# cpu.net
KiCad netlist of a schematic drawn in Altium Designer
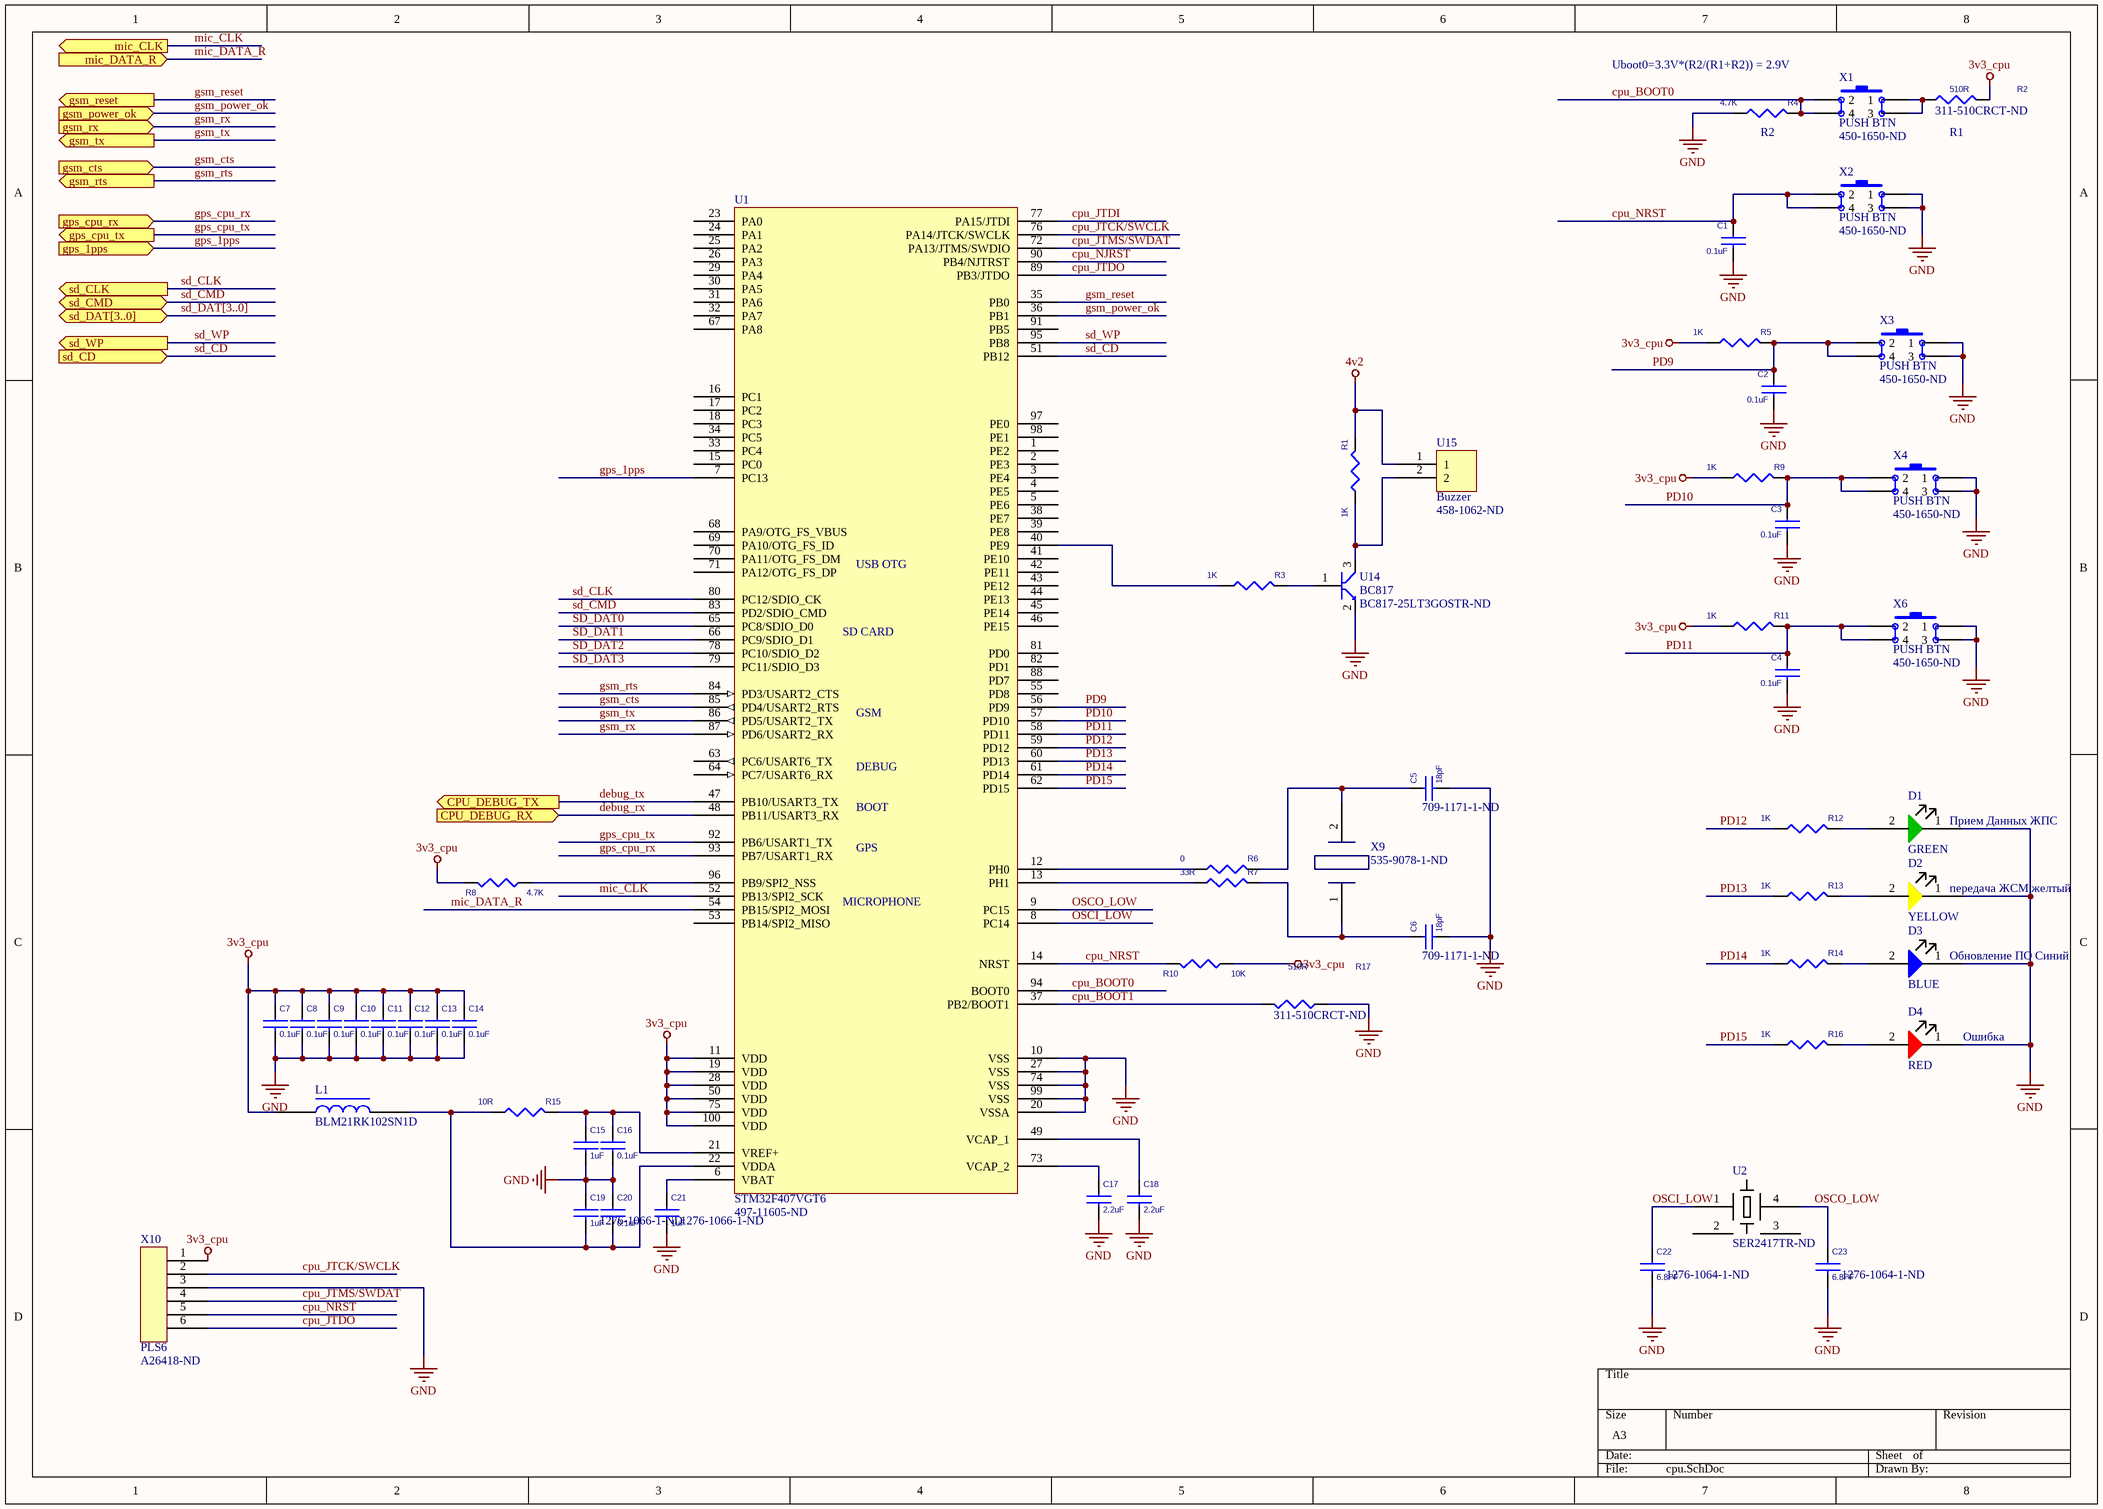
[diagram p0: cpu.SchDoc]

(export (version "E")
  (design (tool "Eeschema 10.0.6"))
  (components
    (comp (ref "C1")
      (value "0.1uF")
      (footprint "CAPC2012X09M")
      (description "CAP CER 0.1UF 25V 10% X7R 0805")
      (libsource (lib "Capacitors") (part "CAP_SMD_0.1UF_10%"))
    )
    (comp (ref "C2")
      (value "0.1uF")
      (footprint "CAPC2012X09M")
      (description "CAP CER 0.1UF 25V 10% X7R 0805")
      (libsource (lib "Capacitors") (part "CAP_SMD_0.1UF_10%"))
    )
    (comp (ref "C3")
      (value "0.1uF")
      (footprint "CAPC2012X09M")
      (description "CAP CER 0.1UF 25V 10% X7R 0805")
      (libsource (lib "Capacitors") (part "CAP_SMD_0.1UF_10%"))
    )
    (comp (ref "C4")
      (value "0.1uF")
      (footprint "CAPC2012X09M")
      (description "CAP CER 0.1UF 25V 10% X7R 0805")
      (libsource (lib "Capacitors") (part "CAP_SMD_0.1UF_10%"))
    )
    (comp (ref "C5")
      (value "18pF")
      (footprint "CAPC2012X09M")
      (description "CAP CER 27PF 200V 5% NP0 0805")
      (fields (field (name "SUPPLIER PART NUMBER 1") "709-1171-1-ND"))
      (libsource (lib "Capacitors") (part "CAP_SMD_18PF_5%"))
    )
    (comp (ref "C6")
      (value "18pF")
      (footprint "CAPC2012X09M")
      (description "CAP CER 27PF 200V 5% NP0 0805")
      (fields (field (name "SUPPLIER PART NUMBER 1") "709-1171-1-ND"))
      (libsource (lib "Capacitors") (part "CAP_SMD_18PF_5%"))
    )
    (comp (ref "C7")
      (value "0.1uF")
      (footprint "CAPC2012X09M")
      (description "CAP CER 0.1UF 25V 10% X7R 0805")
      (libsource (lib "Capacitors") (part "CAP_SMD_0.1UF_10%"))
    )
    (comp (ref "C8")
      (value "0.1uF")
      (footprint "CAPC2012X09M")
      (description "CAP CER 0.1UF 25V 10% X7R 0805")
      (libsource (lib "Capacitors") (part "CAP_SMD_0.1UF_10%"))
    )
    (comp (ref "C9")
      (value "0.1uF")
      (footprint "CAPC2012X09M")
      (description "CAP CER 0.1UF 25V 10% X7R 0805")
      (libsource (lib "Capacitors") (part "CAP_SMD_0.1UF_10%"))
    )
    (comp (ref "C10")
      (value "0.1uF")
      (footprint "CAPC2012X09M")
      (description "CAP CER 0.1UF 25V 10% X7R 0805")
      (libsource (lib "Capacitors") (part "CAP_SMD_0.1UF_10%"))
    )
    (comp (ref "C11")
      (value "0.1uF")
      (footprint "CAPC2012X09M")
      (description "CAP CER 0.1UF 25V 10% X7R 0805")
      (libsource (lib "Capacitors") (part "CAP_SMD_0.1UF_10%"))
    )
    (comp (ref "C12")
      (value "0.1uF")
      (footprint "CAPC2012X09M")
      (description "CAP CER 0.1UF 25V 10% X7R 0805")
      (libsource (lib "Capacitors") (part "CAP_SMD_0.1UF_10%"))
    )
    (comp (ref "C13")
      (value "0.1uF")
      (footprint "CAPC2012X09M")
      (description "CAP CER 0.1UF 25V 10% X7R 0805")
      (libsource (lib "Capacitors") (part "CAP_SMD_0.1UF_10%"))
    )
    (comp (ref "C14")
      (value "0.1uF")
      (footprint "CAPC2012X09M")
      (description "CAP CER 0.1UF 25V 10% X7R 0805")
      (libsource (lib "Capacitors") (part "CAP_SMD_0.1UF_10%"))
    )
    (comp (ref "C15")
      (value "1uF")
      (footprint "CAPC2012X09M")
      (description "MLCC; 1uF; 25V; X7R; ±10%; SMD; 0805;")
      (libsource (lib "Capacitors") (part "CAP_SMD_1uF_10%"))
    )
    (comp (ref "C16")
      (value "0.1uF")
      (footprint "CAPC2012X09M")
      (description "CAP CER 0.1UF 25V 10% X7R 0805")
      (libsource (lib "Capacitors") (part "CAP_SMD_0.1UF_10%"))
    )
    (comp (ref "C17")
      (value "2.2uF")
      (footprint "CAPC2012X09M")
      (description "CAP CER 2.2UF 16V 10% X5R 0805")
      (libsource (lib "Capacitors") (part "CAP_SMD_2.2uF_10%"))
    )
    (comp (ref "C18")
      (value "2.2uF")
      (footprint "CAPC2012X09M")
      (description "CAP CER 2.2UF 16V 10% X5R 0805")
      (libsource (lib "Capacitors") (part "CAP_SMD_2.2uF_10%"))
    )
    (comp (ref "C19")
      (value "1uF")
      (footprint "CAPC2012X09M")
      (description "MLCC; 1uF; 25V; X7R; ±10%; SMD; 0805;")
      (fields (field (name "SUPPLIER PART NUMBER 1") "1276-1066-1-ND"))
      (libsource (lib "Capacitors") (part "CAP_SMD_1uF_10%"))
    )
    (comp (ref "C20")
      (value "0.1uF")
      (footprint "CAPC2012X09M")
      (description "CAP CER 0.1UF 25V 10% X7R 0805")
      (libsource (lib "Capacitors") (part "CAP_SMD_0.1UF_10%"))
    )
    (comp (ref "C21")
      (value "1uF")
      (footprint "CAPC2012X09M")
      (description "MLCC; 1uF; 25V; X7R; ±10%; SMD; 0805;")
      (fields (field (name "SUPPLIER PART NUMBER 1") "1276-1066-1-ND"))
      (libsource (lib "Capacitors") (part "CAP_SMD_1uF_10%"))
    )
    (comp (ref "C22")
      (value "6.8PF")
      (footprint "CAPC2012X09M")
      (description "CAP MLCC 6.8PF 50V 5% NP0 0805")
      (fields (field (name "SUPPLIER PART NUMBER 1") "1276-1064-1-ND"))
      (libsource (lib "Capacitors") (part "CAP_SMD_6.8PF_5%"))
    )
    (comp (ref "C23")
      (value "6.8PF")
      (footprint "CAPC2012X09M")
      (description "CAP MLCC 6.8PF 50V 5% NP0 0805")
      (fields (field (name "SUPPLIER PART NUMBER 1") "1276-1064-1-ND"))
      (libsource (lib "Capacitors") (part "CAP_SMD_6.8PF_5%"))
    )
    (comp (ref "D1")
      (value "GREEN")
      (footprint "DIOC2012X11N")
      (libsource (lib "Passive") (part "LED_GREEN"))
    )
    (comp (ref "D2")
      (value "YELLOW")
      (footprint "DIOC2012X11N")
      (libsource (lib "Passive") (part "LED_YELLOW"))
    )
    (comp (ref "D3") (value "BLUE") (footprint "DIOC2012X11N") (libsource (lib "Passive") (part "LED_BLUE")))
    (comp (ref "D4") (value "RED") (footprint "DIOC2012X11N") (libsource (lib "Passive") (part "LED_RED")))
    (comp (ref "L1")
      (value "BLM21RK102SN1D")
      (footprint "DIOC2012X11N")
      (libsource (lib "Passive") (part "BLM21RK102SN1D"))
    )
    (comp (ref "R1")
      (value "1K")
      (footprint "RESC2013X06M")
      (description "RES - 1K OHM, 5%, 1/8W, 0805 SMD")
      (libsource (lib "Resistors") (part "RES_SMD_1K_5%"))
    )
    (comp (ref "R2")
      (value "510R")
      (footprint "RESC2013X06M")
      (description "RES - 510 OHM, 5%, 1/8W, 0805 SMD")
      (fields (field (name "SUPPLIER PART NUMBER 1") "311-510CRCT-ND"))
      (libsource (lib "Resistors") (part "RES_SMD_510_5%"))
    )
    (comp (ref "R3")
      (value "1K")
      (footprint "RESC2013X06M")
      (description "RES - 1K OHM, 5%, 1/8W, 0805 SMD")
      (libsource (lib "Resistors") (part "RES_SMD_1K_5%"))
    )
    (comp (ref "R4")
      (value "4.7K")
      (footprint "RESC2013X06M")
      (description "RES 4.7K OHM 1/8W 1% 0805 SMD")
      (libsource (lib "Resistors") (part "RES_SMD_4.7K_1%"))
    )
    (comp (ref "R5")
      (value "1K")
      (footprint "RESC2013X06M")
      (description "RES - 1K OHM, 5%, 1/8W, 0805 SMD")
      (libsource (lib "Resistors") (part "RES_SMD_1K_5%"))
    )
    (comp (ref "R6")
      (value "0")
      (footprint "RESC2013X06M")
      (description "RES 0.0 OHM 1/8W JUMP 0805 SMD")
      (libsource (lib "Resistors") (part "RES_SMD_0"))
    )
    (comp (ref "R7")
      (value "33R")
      (footprint "RESC2013X06M")
      (description "RES - 33 OHM, 5%, 1/8W, 0805 SMD")
      (libsource (lib "Resistors") (part "RES_SMD_33R_5%"))
    )
    (comp (ref "R8")
      (value "4.7K")
      (footprint "RESC2013X06M")
      (description "RES 4.7K OHM 1/8W 1% 0805 SMD")
      (libsource (lib "Resistors") (part "RES_SMD_4.7K_1%"))
    )
    (comp (ref "R9")
      (value "1K")
      (footprint "RESC2013X06M")
      (description "RES - 1K OHM, 5%, 1/8W, 0805 SMD")
      (libsource (lib "Resistors") (part "RES_SMD_1K_5%"))
    )
    (comp (ref "R10")
      (value "10K")
      (footprint "RESC2013X06M")
      (description "RES 10K OHM 1/8W 5% 0805 SMD")
      (libsource (lib "Resistors") (part "RES_SMD_10K_5%"))
    )
    (comp (ref "R11")
      (value "1K")
      (footprint "RESC2013X06M")
      (description "RES - 1K OHM, 5%, 1/8W, 0805 SMD")
      (libsource (lib "Resistors") (part "RES_SMD_1K_5%"))
    )
    (comp (ref "R12")
      (value "1K")
      (footprint "RESC2013X06M")
      (description "RES - 1K OHM, 5%, 1/8W, 0805 SMD")
      (libsource (lib "Resistors") (part "RES_SMD_1K_5%"))
    )
    (comp (ref "R13")
      (value "1K")
      (footprint "RESC2013X06M")
      (description "RES - 1K OHM, 5%, 1/8W, 0805 SMD")
      (libsource (lib "Resistors") (part "RES_SMD_1K_5%"))
    )
    (comp (ref "R14")
      (value "1K")
      (footprint "RESC2013X06M")
      (description "RES - 1K OHM, 5%, 1/8W, 0805 SMD")
      (libsource (lib "Resistors") (part "RES_SMD_1K_5%"))
    )
    (comp (ref "R15")
      (value "10R")
      (footprint "RESC2013X06M")
      (description "RES 10 OHM 1/8W 1% 0805 SMD")
      (libsource (lib "Resistors") (part "RES_SMD_10R_5%"))
    )
    (comp (ref "R16")
      (value "1K")
      (footprint "RESC2013X06M")
      (description "RES - 1K OHM, 5%, 1/8W, 0805 SMD")
      (libsource (lib "Resistors") (part "RES_SMD_1K_5%"))
    )
    (comp (ref "R17")
      (value "510R")
      (footprint "RESC2013X06M")
      (description "RES - 510 OHM, 5%, 1/8W, 0805 SMD")
      (fields (field (name "SUPPLIER PART NUMBER 1") "311-510CRCT-ND"))
      (libsource (lib "Resistors") (part "RES_SMD_510_5%"))
    )
    (comp (ref "U1")
      (value "STM32F407VGT6")
      (footprint "TSQFP50P1600X1600X160-100M")
      (fields (field (name "SUPPLIER PART NUMBER 1") "497-11605-ND"))
      (libsource (lib "TruthEar") (part "STM32F407VGT6"))
    )
    (comp (ref "U2")
      (value "32.768KHZ")
      (footprint "SOJ550P380X254-4M")
      (fields (field (name "SUPPLIER PART NUMBER 1") "SER2417TR-ND"))
      (libsource (lib "TruthEar") (part "MC-306"))
    )
    (comp (ref "U14")
      (value "BC817")
      (footprint "SOT95P237X111-3N_SOT-23")
      (fields (field (name "SUPPLIER PART NUMBER 1") "BC817-25LT3GOSTR-ND"))
      (libsource (lib "TruthEar") (part "BC817"))
    )
    (comp (ref "U15")
      (value "Buzzer")
      (footprint "pb1224pe")
      (fields (field (name "SUPPLIER PART NUMBER 1") "458-1062-ND"))
      (libsource (lib "TruthEar") (part "pb-1224pe-05q"))
    )
    (comp (ref "X1")
      (value "PUSH BTN")
      (footprint "PUSHBTN")
      (fields (field (name "SUPPLIER PART NUMBER 1") "450-1650-ND"))
      (libsource (lib "TruthEar") (part "SW1"))
    )
    (comp (ref "X2")
      (value "PUSH BTN")
      (footprint "PUSHBTN")
      (fields (field (name "SUPPLIER PART NUMBER 1") "450-1650-ND"))
      (libsource (lib "TruthEar") (part "SW1"))
    )
    (comp (ref "X3")
      (value "PUSH BTN")
      (footprint "PUSHBTN")
      (fields (field (name "SUPPLIER PART NUMBER 1") "450-1650-ND"))
      (libsource (lib "TruthEar") (part "SW1"))
    )
    (comp (ref "X4")
      (value "PUSH BTN")
      (footprint "PUSHBTN")
      (fields (field (name "SUPPLIER PART NUMBER 1") "450-1650-ND"))
      (libsource (lib "TruthEar") (part "SW1"))
    )
    (comp (ref "X6")
      (value "PUSH BTN")
      (footprint "PUSHBTN")
      (fields (field (name "SUPPLIER PART NUMBER 1") "450-1650-ND"))
      (libsource (lib "TruthEar") (part "SW1"))
    )
    (comp (ref "X9")
      (value "25.000Mhz")
      (footprint "SODFL1270X420-2L")
      (fields (field (name "SUPPLIER PART NUMBER 1") "535-9078-1-ND"))
      (libsource (lib "TruthEar") (part "OSC25M"))
    )
    (comp (ref "X10")
      (value "PLS6")
      (footprint "PLS6")
      (fields (field (name "SUPPLIER PART NUMBER 1") "A26418-ND"))
      (libsource (lib "Connectors") (part "PLS6"))
    )
  )
  (nets
    (net (code "5") (name "/OSCI_LOW") (class "Default")
      (node (ref "C22") (pin "1") (pinfunction "1_1") (pintype "passive"))
      (node (ref "U1") (pin "8") (pinfunction "PC14_8") (pintype "passive"))
      (node (ref "U2") (pin "1") (pinfunction "OSC1_1") (pintype "power_in"))
    )
    (net (code "6") (name "/OSCO_LOW") (class "Default")
      (node (ref "C23") (pin "1") (pinfunction "1_1") (pintype "passive"))
      (node (ref "U1") (pin "9") (pinfunction "PC15_9") (pintype "passive"))
      (node (ref "U2") (pin "4") (pinfunction "OSC2_4") (pintype "power_in"))
    )
    (net (code "7") (name "/PD9") (class "Default")
      (node (ref "C2") (pin "1") (pinfunction "1_1") (pintype "passive"))
      (node (ref "R5") (pin "2") (pinfunction "2_2") (pintype "passive"))
      (node (ref "U1") (pin "56") (pinfunction "PD9_56") (pintype "passive"))
      (node (ref "X3") (pin "2") (pinfunction "2_2") (pintype "passive"))
      (node (ref "X3") (pin "4") (pinfunction "4_4") (pintype "passive"))
    )
    (net (code "8") (name "/PD10") (class "Default")
      (node (ref "C3") (pin "1") (pinfunction "1_1") (pintype "passive"))
      (node (ref "R9") (pin "2") (pinfunction "2_2") (pintype "passive"))
      (node (ref "U1") (pin "57") (pinfunction "PD10_57") (pintype "passive"))
      (node (ref "X4") (pin "2") (pinfunction "2_2") (pintype "passive"))
      (node (ref "X4") (pin "4") (pinfunction "4_4") (pintype "passive"))
    )
    (net (code "9") (name "/PD11") (class "Default")
      (node (ref "C4") (pin "1") (pinfunction "1_1") (pintype "passive"))
      (node (ref "R11") (pin "2") (pinfunction "2_2") (pintype "passive"))
      (node (ref "U1") (pin "58") (pinfunction "PD11_58") (pintype "passive"))
      (node (ref "X6") (pin "2") (pinfunction "2_2") (pintype "passive"))
      (node (ref "X6") (pin "4") (pinfunction "4_4") (pintype "passive"))
    )
    (net (code "10") (name "/PD12") (class "Default")
      (node (ref "R12") (pin "1") (pinfunction "1_1") (pintype "passive"))
      (node (ref "U1") (pin "59") (pinfunction "PD12_59") (pintype "passive"))
    )
    (net (code "11") (name "/PD13") (class "Default")
      (node (ref "R13") (pin "1") (pinfunction "1_1") (pintype "passive"))
      (node (ref "U1") (pin "60") (pinfunction "PD13_60") (pintype "passive"))
    )
    (net (code "12") (name "/PD14") (class "Default")
      (node (ref "R14") (pin "1") (pinfunction "1_1") (pintype "passive"))
      (node (ref "U1") (pin "61") (pinfunction "PD14_61") (pintype "passive"))
    )
    (net (code "13") (name "/PD15") (class "Default")
      (node (ref "R16") (pin "1") (pinfunction "1_1") (pintype "passive"))
      (node (ref "U1") (pin "62") (pinfunction "PD15_62") (pintype "passive"))
    )
    (net (code "14") (name "/SD_DAT0") (class "Default")
      (node (ref "U1") (pin "65") (pinfunction "PC8/SDIO_D0_65") (pintype "passive"))
    )
    (net (code "15") (name "/SD_DAT1") (class "Default")
      (node (ref "U1") (pin "66") (pinfunction "PC9/SDIO_D1_66") (pintype "passive"))
    )
    (net (code "16") (name "/SD_DAT2") (class "Default")
      (node (ref "U1") (pin "78") (pinfunction "PC10/SDIO_D2_78") (pintype "passive"))
    )
    (net (code "17") (name "/SD_DAT3") (class "Default")
      (node (ref "U1") (pin "79") (pinfunction "PC11/SDIO_D3_79") (pintype "passive"))
    )
    (net (code "18") (name "/cpu_BOOT0") (class "Default")
      (node (ref "R4") (pin "2") (pinfunction "2_2") (pintype "passive"))
      (node (ref "U1") (pin "94") (pinfunction "BOOT0_94") (pintype "passive"))
      (node (ref "X1") (pin "2") (pinfunction "2_2") (pintype "passive"))
      (node (ref "X1") (pin "4") (pinfunction "4_4") (pintype "passive"))
    )
    (net (code "19") (name "/cpu_BOOT1") (class "Default")
      (node (ref "R17") (pin "2") (pinfunction "2_2") (pintype "passive"))
      (node (ref "U1") (pin "37") (pinfunction "PB2/BOOT1_37") (pintype "passive"))
    )
    (net (code "20") (name "/cpu_JTCK{slash}SWCLK") (class "Default")
      (node (ref "U1") (pin "76") (pinfunction "PA14/JTCK/SWCLK_76") (pintype "passive"))
      (node (ref "X10") (pin "2") (pinfunction "2_2") (pintype "power_in"))
    )
    (net (code "21") (name "/cpu_JTDI") (class "Default")
      (node (ref "U1") (pin "77") (pinfunction "PA15/JTDI_77") (pintype "passive"))
    )
    (net (code "22") (name "/cpu_JTDO") (class "Default")
      (node (ref "U1") (pin "89") (pinfunction "PB3/JTDO_89") (pintype "passive"))
      (node (ref "X10") (pin "6") (pinfunction "6_6") (pintype "power_in"))
    )
    (net (code "23") (name "/cpu_JTMS{slash}SWDAT") (class "Default")
      (node (ref "U1") (pin "72") (pinfunction "PA13/JTMS/SWDIO_72") (pintype "passive"))
      (node (ref "X10") (pin "4") (pinfunction "4_4") (pintype "power_in"))
    )
    (net (code "24") (name "/cpu_NJRST") (class "Default")
      (node (ref "U1") (pin "90") (pinfunction "PB4/NJTRST_90") (pintype "passive"))
    )
    (net (code "25") (name "/cpu_NRST") (class "Default")
      (node (ref "C1") (pin "1") (pinfunction "1_1") (pintype "passive"))
      (node (ref "R10") (pin "2") (pinfunction "2_2") (pintype "passive"))
      (node (ref "U1") (pin "14") (pinfunction "NRST_14") (pintype "passive"))
      (node (ref "X10") (pin "5") (pinfunction "5_5") (pintype "power_in"))
      (node (ref "X2") (pin "2") (pinfunction "2_2") (pintype "passive"))
      (node (ref "X2") (pin "4") (pinfunction "4_4") (pintype "passive"))
    )
    (net (code "26") (name "/debug_rx") (class "Default")
      (node (ref "U1") (pin "48") (pinfunction "PB11/USART3_RX_48") (pintype "passive"))
    )
    (net (code "27") (name "/debug_tx") (class "Default")
      (node (ref "U1") (pin "47") (pinfunction "PB10/USART3_TX_47") (pintype "passive"))
    )
    (net (code "28") (name "/gps_1pps") (class "Default")
      (node (ref "U1") (pin "7") (pinfunction "PC13_7") (pintype "passive"))
    )
    (net (code "29") (name "/gps_cpu_rx") (class "Default")
      (node (ref "U1") (pin "93") (pinfunction "PB7/USART1_RX_93") (pintype "passive"))
    )
    (net (code "30") (name "/gps_cpu_tx") (class "Default")
      (node (ref "U1") (pin "92") (pinfunction "PB6/USART1_TX_92") (pintype "passive"))
    )
    (net (code "31") (name "/gsm_cts") (class "Default")
      (node (ref "U1") (pin "85") (pinfunction "PD4/USART2_RTS_85") (pintype "output"))
    )
    (net (code "32") (name "/gsm_power_ok") (class "Default")
      (node (ref "U1") (pin "36") (pinfunction "PB1_36") (pintype "passive"))
    )
    (net (code "33") (name "/gsm_reset") (class "Default")
      (node (ref "U1") (pin "35") (pinfunction "PB0_35") (pintype "passive"))
    )
    (net (code "34") (name "/gsm_rts") (class "Default")
      (node (ref "U1") (pin "84") (pinfunction "PD3/USART2_CTS_84") (pintype "input"))
    )
    (net (code "35") (name "/gsm_rx") (class "Default")
      (node (ref "U1") (pin "87") (pinfunction "PD6/USART2_RX_87") (pintype "input"))
    )
    (net (code "36") (name "/gsm_tx") (class "Default")
      (node (ref "U1") (pin "86") (pinfunction "PD5/USART2_TX_86") (pintype "output"))
    )
    (net (code "37") (name "/mic_CLK") (class "Default")
      (node (ref "U1") (pin "52") (pinfunction "PB13/SPI2_SCK_52") (pintype "passive"))
    )
    (net (code "38") (name "/mic_DATA_R") (class "Default")
      (node (ref "U1") (pin "54") (pinfunction "PB15/SPI2_MOSI_54") (pintype "passive"))
    )
    (net (code "39") (name "/sd_CD") (class "Default")
      (node (ref "U1") (pin "51") (pinfunction "PB12_51") (pintype "passive"))
    )
    (net (code "40") (name "/sd_CLK") (class "Default")
      (node (ref "U1") (pin "80") (pinfunction "PC12/SDIO_CK_80") (pintype "passive"))
    )
    (net (code "41") (name "/sd_CMD") (class "Default")
      (node (ref "U1") (pin "83") (pinfunction "PD2/SDIO_CMD_83") (pintype "passive"))
    )
    (net (code "43") (name "/sd_WP") (class "Default")
      (node (ref "U1") (pin "95") (pinfunction "PB8_95") (pintype "passive"))
    )
    (net (code "44") (name "3v3_cpu") (class "Default")
      (node (ref "C10") (pin "1") (pinfunction "1_1") (pintype "passive"))
      (node (ref "C11") (pin "1") (pinfunction "1_1") (pintype "passive"))
      (node (ref "C12") (pin "1") (pinfunction "1_1") (pintype "passive"))
      (node (ref "C13") (pin "1") (pinfunction "1_1") (pintype "passive"))
      (node (ref "C14") (pin "1") (pinfunction "1_1") (pintype "passive"))
      (node (ref "C7") (pin "1") (pinfunction "1_1") (pintype "passive"))
      (node (ref "C8") (pin "1") (pinfunction "1_1") (pintype "passive"))
      (node (ref "C9") (pin "1") (pinfunction "1_1") (pintype "passive"))
      (node (ref "L1") (pin "1") (pinfunction "1_1") (pintype "passive"))
      (node (ref "R10") (pin "1") (pinfunction "1_1") (pintype "passive"))
      (node (ref "R11") (pin "1") (pinfunction "1_1") (pintype "passive"))
      (node (ref "R2") (pin "1") (pinfunction "1_1") (pintype "passive"))
      (node (ref "R5") (pin "1") (pinfunction "1_1") (pintype "passive"))
      (node (ref "R8") (pin "2") (pinfunction "2_2") (pintype "passive"))
      (node (ref "R9") (pin "1") (pinfunction "1_1") (pintype "passive"))
      (node (ref "U1") (pin "100") (pinfunction "VDD_100") (pintype "passive"))
      (node (ref "U1") (pin "11") (pinfunction "VDD_11") (pintype "passive"))
      (node (ref "U1") (pin "19") (pinfunction "VDD_19") (pintype "passive"))
      (node (ref "U1") (pin "28") (pinfunction "VDD_28") (pintype "passive"))
      (node (ref "U1") (pin "50") (pinfunction "VDD_50") (pintype "passive"))
      (node (ref "U1") (pin "75") (pinfunction "VDD_75") (pintype "passive"))
      (node (ref "X10") (pin "1") (pinfunction "1_1") (pintype "power_in"))
    )
    (net (code "45") (name "4v2") (class "Default")
      (node (ref "R1") (pin "2") (pinfunction "2_2") (pintype "passive"))
      (node (ref "U15") (pin "1") (pinfunction "1_1") (pintype "passive"))
    )
    (net (code "46") (name "GND") (class "Default")
      (node (ref "C1") (pin "2") (pinfunction "2_2") (pintype "passive"))
      (node (ref "C10") (pin "2") (pinfunction "2_2") (pintype "passive"))
      (node (ref "C11") (pin "2") (pinfunction "2_2") (pintype "passive"))
      (node (ref "C12") (pin "2") (pinfunction "2_2") (pintype "passive"))
      (node (ref "C13") (pin "2") (pinfunction "2_2") (pintype "passive"))
      (node (ref "C14") (pin "2") (pinfunction "2_2") (pintype "passive"))
      (node (ref "C15") (pin "2") (pinfunction "2_2") (pintype "passive"))
      (node (ref "C16") (pin "2") (pinfunction "2_2") (pintype "passive"))
      (node (ref "C17") (pin "2") (pinfunction "2_2") (pintype "passive"))
      (node (ref "C18") (pin "2") (pinfunction "2_2") (pintype "passive"))
      (node (ref "C19") (pin "1") (pinfunction "1_1") (pintype "passive"))
      (node (ref "C2") (pin "2") (pinfunction "2_2") (pintype "passive"))
      (node (ref "C20") (pin "1") (pinfunction "1_1") (pintype "passive"))
      (node (ref "C21") (pin "2") (pinfunction "2_2") (pintype "passive"))
      (node (ref "C22") (pin "2") (pinfunction "2_2") (pintype "passive"))
      (node (ref "C23") (pin "2") (pinfunction "2_2") (pintype "passive"))
      (node (ref "C3") (pin "2") (pinfunction "2_2") (pintype "passive"))
      (node (ref "C4") (pin "2") (pinfunction "2_2") (pintype "passive"))
      (node (ref "C5") (pin "2") (pinfunction "2_2") (pintype "passive"))
      (node (ref "C6") (pin "2") (pinfunction "2_2") (pintype "passive"))
      (node (ref "C7") (pin "2") (pinfunction "2_2") (pintype "passive"))
      (node (ref "C8") (pin "2") (pinfunction "2_2") (pintype "passive"))
      (node (ref "C9") (pin "2") (pinfunction "2_2") (pintype "passive"))
      (node (ref "D1") (pin "1") (pinfunction "C_1") (pintype "passive"))
      (node (ref "D2") (pin "1") (pinfunction "C_1") (pintype "passive"))
      (node (ref "D3") (pin "1") (pinfunction "C_1") (pintype "passive"))
      (node (ref "D4") (pin "1") (pinfunction "C_1") (pintype "passive"))
      (node (ref "R17") (pin "1") (pinfunction "1_1") (pintype "passive"))
      (node (ref "R4") (pin "1") (pinfunction "1_1") (pintype "passive"))
      (node (ref "U1") (pin "10") (pinfunction "VSS_10") (pintype "passive"))
      (node (ref "U1") (pin "20") (pinfunction "VSSA_20") (pintype "passive"))
      (node (ref "U1") (pin "27") (pinfunction "VSS_27") (pintype "passive"))
      (node (ref "U1") (pin "74") (pinfunction "VSS_74") (pintype "passive"))
      (node (ref "U1") (pin "99") (pinfunction "VSS_99") (pintype "passive"))
      (node (ref "U14") (pin "2") (pinfunction "E_2") (pintype "passive"))
      (node (ref "X10") (pin "3") (pinfunction "3_3") (pintype "power_in"))
      (node (ref "X2") (pin "1") (pinfunction "1_1") (pintype "passive"))
      (node (ref "X2") (pin "3") (pinfunction "3_3") (pintype "passive"))
      (node (ref "X3") (pin "1") (pinfunction "1_1") (pintype "passive"))
      (node (ref "X3") (pin "3") (pinfunction "3_3") (pintype "passive"))
      (node (ref "X4") (pin "1") (pinfunction "1_1") (pintype "passive"))
      (node (ref "X4") (pin "3") (pinfunction "3_3") (pintype "passive"))
      (node (ref "X6") (pin "1") (pinfunction "1_1") (pintype "passive"))
      (node (ref "X6") (pin "3") (pinfunction "3_3") (pintype "passive"))
    )
    (net (code "47") (name "Net-(C5-Pad1)") (class "Default")
      (node (ref "C5") (pin "1") (pinfunction "1_1") (pintype "passive"))
      (node (ref "R6") (pin "2") (pinfunction "2_2") (pintype "passive"))
      (node (ref "X9") (pin "2") (pinfunction "2_2") (pintype "power_in"))
    )
    (net (code "48") (name "Net-(C6-Pad1)") (class "Default")
      (node (ref "C6") (pin "1") (pinfunction "1_1") (pintype "passive"))
      (node (ref "R7") (pin "2") (pinfunction "2_2") (pintype "passive"))
      (node (ref "X9") (pin "1") (pinfunction "1_1") (pintype "power_in"))
    )
    (net (code "49") (name "Net-(D1-A)") (class "Default")
      (node (ref "D1") (pin "2") (pinfunction "A_2") (pintype "passive"))
      (node (ref "R12") (pin "2") (pinfunction "2_2") (pintype "passive"))
    )
    (net (code "50") (name "Net-(D2-A)") (class "Default")
      (node (ref "D2") (pin "2") (pinfunction "A_2") (pintype "passive"))
      (node (ref "R13") (pin "2") (pinfunction "2_2") (pintype "passive"))
    )
    (net (code "51") (name "Net-(D3-A)") (class "Default")
      (node (ref "D3") (pin "2") (pinfunction "A_2") (pintype "passive"))
      (node (ref "R14") (pin "2") (pinfunction "2_2") (pintype "passive"))
    )
    (net (code "52") (name "Net-(D4-A)") (class "Default")
      (node (ref "D4") (pin "2") (pinfunction "A_2") (pintype "passive"))
      (node (ref "R16") (pin "2") (pinfunction "2_2") (pintype "passive"))
    )
    (net (code "53") (name "Net-(R2-Pad2)") (class "Default")
      (node (ref "R2") (pin "2") (pinfunction "2_2") (pintype "passive"))
      (node (ref "X1") (pin "1") (pinfunction "1_1") (pintype "passive"))
      (node (ref "X1") (pin "3") (pinfunction "3_3") (pintype "passive"))
    )
    (net (code "54") (name "Net-(U1-PB9{slash}SPI2_NSS)") (class "Default")
      (node (ref "R8") (pin "1") (pinfunction "1_1") (pintype "passive"))
      (node (ref "U1") (pin "96") (pinfunction "PB9/SPI2_NSS_96") (pintype "passive"))
    )
    (net (code "55") (name "Net-(U1-PE9)") (class "Default")
      (node (ref "R3") (pin "1") (pinfunction "1_1") (pintype "passive"))
      (node (ref "U1") (pin "40") (pinfunction "PE9_40") (pintype "passive"))
    )
    (net (code "56") (name "Net-(U1-PH0)") (class "Default")
      (node (ref "R6") (pin "1") (pinfunction "1_1") (pintype "passive"))
      (node (ref "U1") (pin "12") (pinfunction "PH0_12") (pintype "passive"))
    )
    (net (code "57") (name "Net-(U1-PH1)") (class "Default")
      (node (ref "R7") (pin "1") (pinfunction "1_1") (pintype "passive"))
      (node (ref "U1") (pin "13") (pinfunction "PH1_13") (pintype "passive"))
    )
    (net (code "58") (name "Net-(U1-VBAT)") (class "Default")
      (node (ref "C21") (pin "1") (pinfunction "1_1") (pintype "passive"))
      (node (ref "U1") (pin "6") (pinfunction "VBAT_6") (pintype "passive"))
    )
    (net (code "59") (name "Net-(U1-VCAP_1)") (class "Default")
      (node (ref "C18") (pin "1") (pinfunction "1_1") (pintype "passive"))
      (node (ref "U1") (pin "49") (pinfunction "VCAP_1_49") (pintype "passive"))
    )
    (net (code "60") (name "Net-(U1-VCAP_2)") (class "Default")
      (node (ref "C17") (pin "1") (pinfunction "1_1") (pintype "passive"))
      (node (ref "U1") (pin "73") (pinfunction "VCAP_2_73") (pintype "passive"))
    )
    (net (code "61") (name "Net-(U1-VDDA)") (class "Default")
      (node (ref "C19") (pin "2") (pinfunction "2_2") (pintype "passive"))
      (node (ref "C20") (pin "2") (pinfunction "2_2") (pintype "passive"))
      (node (ref "L1") (pin "2") (pinfunction "2_2") (pintype "passive"))
      (node (ref "R15") (pin "1") (pinfunction "1_1") (pintype "passive"))
      (node (ref "U1") (pin "22") (pinfunction "VDDA_22") (pintype "passive"))
    )
    (net (code "62") (name "Net-(U1-VREF+)") (class "Default")
      (node (ref "C15") (pin "1") (pinfunction "1_1") (pintype "passive"))
      (node (ref "C16") (pin "1") (pinfunction "1_1") (pintype "passive"))
      (node (ref "R15") (pin "2") (pinfunction "2_2") (pintype "passive"))
      (node (ref "U1") (pin "21") (pinfunction "VREF+_21") (pintype "passive"))
    )
    (net (code "63") (name "Net-(U14-B)") (class "Default")
      (node (ref "R3") (pin "2") (pinfunction "2_2") (pintype "passive"))
      (node (ref "U14") (pin "1") (pinfunction "B_1") (pintype "passive"))
    )
    (net (code "64") (name "Net-(U14-C)") (class "Default")
      (node (ref "R1") (pin "1") (pinfunction "1_1") (pintype "passive"))
      (node (ref "U14") (pin "3") (pinfunction "C_3") (pintype "passive"))
      (node (ref "U15") (pin "2") (pinfunction "2_2") (pintype "passive"))
    )
    (net (code "65") (name "unconnected-(U1-PA0-Pad23)") (class "Default")
      (node (ref "U1") (pin "23") (pinfunction "PA0_23") (pintype "passive"))
    )
    (net (code "66") (name "unconnected-(U1-PA1-Pad24)") (class "Default")
      (node (ref "U1") (pin "24") (pinfunction "PA1_24") (pintype "passive"))
    )
    (net (code "67") (name "unconnected-(U1-PA2-Pad25)") (class "Default")
      (node (ref "U1") (pin "25") (pinfunction "PA2_25") (pintype "passive"))
    )
    (net (code "68") (name "unconnected-(U1-PA3-Pad26)") (class "Default")
      (node (ref "U1") (pin "26") (pinfunction "PA3_26") (pintype "passive"))
    )
    (net (code "69") (name "unconnected-(U1-PA4-Pad29)") (class "Default")
      (node (ref "U1") (pin "29") (pinfunction "PA4_29") (pintype "passive"))
    )
    (net (code "70") (name "unconnected-(U1-PA5-Pad30)") (class "Default")
      (node (ref "U1") (pin "30") (pinfunction "PA5_30") (pintype "passive"))
    )
    (net (code "71") (name "unconnected-(U1-PA6-Pad31)") (class "Default")
      (node (ref "U1") (pin "31") (pinfunction "PA6_31") (pintype "passive"))
    )
    (net (code "72") (name "unconnected-(U1-PA7-Pad32)") (class "Default")
      (node (ref "U1") (pin "32") (pinfunction "PA7_32") (pintype "passive"))
    )
    (net (code "73") (name "unconnected-(U1-PA8-Pad67)") (class "Default")
      (node (ref "U1") (pin "67") (pinfunction "PA8_67") (pintype "passive"))
    )
    (net (code "74") (name "unconnected-(U1-PA9{slash}OTG_FS_VBUS-Pad68)") (class "Default")
      (node (ref "U1") (pin "68") (pinfunction "PA9/OTG_FS_VBUS_68") (pintype "passive"))
    )
    (net (code "75") (name "unconnected-(U1-PA10{slash}OTG_FS_ID-Pad69)") (class "Default")
      (node (ref "U1") (pin "69") (pinfunction "PA10/OTG_FS_ID_69") (pintype "passive"))
    )
    (net (code "76") (name "unconnected-(U1-PA11{slash}OTG_FS_DM-Pad70)") (class "Default")
      (node (ref "U1") (pin "70") (pinfunction "PA11/OTG_FS_DM_70") (pintype "passive"))
    )
    (net (code "77") (name "unconnected-(U1-PA12{slash}OTG_FS_DP-Pad71)") (class "Default")
      (node (ref "U1") (pin "71") (pinfunction "PA12/OTG_FS_DP_71") (pintype "passive"))
    )
    (net (code "78") (name "unconnected-(U1-PB5-Pad91)") (class "Default")
      (node (ref "U1") (pin "91") (pinfunction "PB5_91") (pintype "passive"))
    )
    (net (code "79") (name "unconnected-(U1-PB14{slash}SPI2_MISO-Pad53)") (class "Default")
      (node (ref "U1") (pin "53") (pinfunction "PB14/SPI2_MISO_53") (pintype "passive"))
    )
    (net (code "80") (name "unconnected-(U1-PC0-Pad15)") (class "Default")
      (node (ref "U1") (pin "15") (pinfunction "PC0_15") (pintype "passive"))
    )
    (net (code "81") (name "unconnected-(U1-PC1-Pad16)") (class "Default")
      (node (ref "U1") (pin "16") (pinfunction "PC1_16") (pintype "passive"))
    )
    (net (code "82") (name "unconnected-(U1-PC2-Pad17)") (class "Default")
      (node (ref "U1") (pin "17") (pinfunction "PC2_17") (pintype "passive"))
    )
    (net (code "83") (name "unconnected-(U1-PC3-Pad18)") (class "Default")
      (node (ref "U1") (pin "18") (pinfunction "PC3_18") (pintype "passive"))
    )
    (net (code "84") (name "unconnected-(U1-PC4-Pad33)") (class "Default")
      (node (ref "U1") (pin "33") (pinfunction "PC4_33") (pintype "passive"))
    )
    (net (code "85") (name "unconnected-(U1-PC5-Pad34)") (class "Default")
      (node (ref "U1") (pin "34") (pinfunction "PC5_34") (pintype "passive"))
    )
    (net (code "86") (name "unconnected-(U1-PC6{slash}USART6_TX-Pad63)") (class "Default")
      (node (ref "U1") (pin "63") (pinfunction "PC6/USART6_TX_63") (pintype "output"))
    )
    (net (code "87") (name "unconnected-(U1-PC7{slash}USART6_RX-Pad64)") (class "Default")
      (node (ref "U1") (pin "64") (pinfunction "PC7/USART6_RX_64") (pintype "input"))
    )
    (net (code "88") (name "unconnected-(U1-PD0-Pad81)") (class "Default")
      (node (ref "U1") (pin "81") (pinfunction "PD0_81") (pintype "passive"))
    )
    (net (code "89") (name "unconnected-(U1-PD1-Pad82)") (class "Default")
      (node (ref "U1") (pin "82") (pinfunction "PD1_82") (pintype "passive"))
    )
    (net (code "90") (name "unconnected-(U1-PD7-Pad88)") (class "Default")
      (node (ref "U1") (pin "88") (pinfunction "PD7_88") (pintype "passive"))
    )
    (net (code "91") (name "unconnected-(U1-PD8-Pad55)") (class "Default")
      (node (ref "U1") (pin "55") (pinfunction "PD8_55") (pintype "passive"))
    )
    (net (code "92") (name "unconnected-(U1-PE0-Pad97)") (class "Default")
      (node (ref "U1") (pin "97") (pinfunction "PE0_97") (pintype "passive"))
    )
    (net (code "93") (name "unconnected-(U1-PE1-Pad98)") (class "Default")
      (node (ref "U1") (pin "98") (pinfunction "PE1_98") (pintype "passive"))
    )
    (net (code "94") (name "unconnected-(U1-PE2-Pad1)") (class "Default")
      (node (ref "U1") (pin "1") (pinfunction "PE2_1") (pintype "passive"))
    )
    (net (code "95") (name "unconnected-(U1-PE3-Pad2)") (class "Default")
      (node (ref "U1") (pin "2") (pinfunction "PE3_2") (pintype "passive"))
    )
    (net (code "96") (name "unconnected-(U1-PE4-Pad3)") (class "Default")
      (node (ref "U1") (pin "3") (pinfunction "PE4_3") (pintype "passive"))
    )
    (net (code "97") (name "unconnected-(U1-PE5-Pad4)") (class "Default")
      (node (ref "U1") (pin "4") (pinfunction "PE5_4") (pintype "passive"))
    )
    (net (code "98") (name "unconnected-(U1-PE6-Pad5)") (class "Default")
      (node (ref "U1") (pin "5") (pinfunction "PE6_5") (pintype "passive"))
    )
    (net (code "99") (name "unconnected-(U1-PE7-Pad38)") (class "Default")
      (node (ref "U1") (pin "38") (pinfunction "PE7_38") (pintype "passive"))
    )
    (net (code "100") (name "unconnected-(U1-PE8-Pad39)") (class "Default")
      (node (ref "U1") (pin "39") (pinfunction "PE8_39") (pintype "passive"))
    )
    (net (code "101") (name "unconnected-(U1-PE10-Pad41)") (class "Default")
      (node (ref "U1") (pin "41") (pinfunction "PE10_41") (pintype "passive"))
    )
    (net (code "102") (name "unconnected-(U1-PE11-Pad42)") (class "Default")
      (node (ref "U1") (pin "42") (pinfunction "PE11_42") (pintype "passive"))
    )
    (net (code "103") (name "unconnected-(U1-PE12-Pad43)") (class "Default")
      (node (ref "U1") (pin "43") (pinfunction "PE12_43") (pintype "passive"))
    )
    (net (code "104") (name "unconnected-(U1-PE13-Pad44)") (class "Default")
      (node (ref "U1") (pin "44") (pinfunction "PE13_44") (pintype "passive"))
    )
    (net (code "105") (name "unconnected-(U1-PE14-Pad45)") (class "Default")
      (node (ref "U1") (pin "45") (pinfunction "PE14_45") (pintype "passive"))
    )
    (net (code "106") (name "unconnected-(U1-PE15-Pad46)") (class "Default")
      (node (ref "U1") (pin "46") (pinfunction "PE15_46") (pintype "passive"))
    )
    (net (code "107") (name "unconnected-(U2-NC-Pad2)") (class "Default")
      (node (ref "U2") (pin "2") (pinfunction "NC_2") (pintype "power_in"))
    )
    (net (code "108") (name "unconnected-(U2-NC-Pad3)") (class "Default")
      (node (ref "U2") (pin "3") (pinfunction "NC_3") (pintype "power_in"))
    )
  )
)
